# FOC.net
KiCad netlist of a schematic drawn in Altium Designer
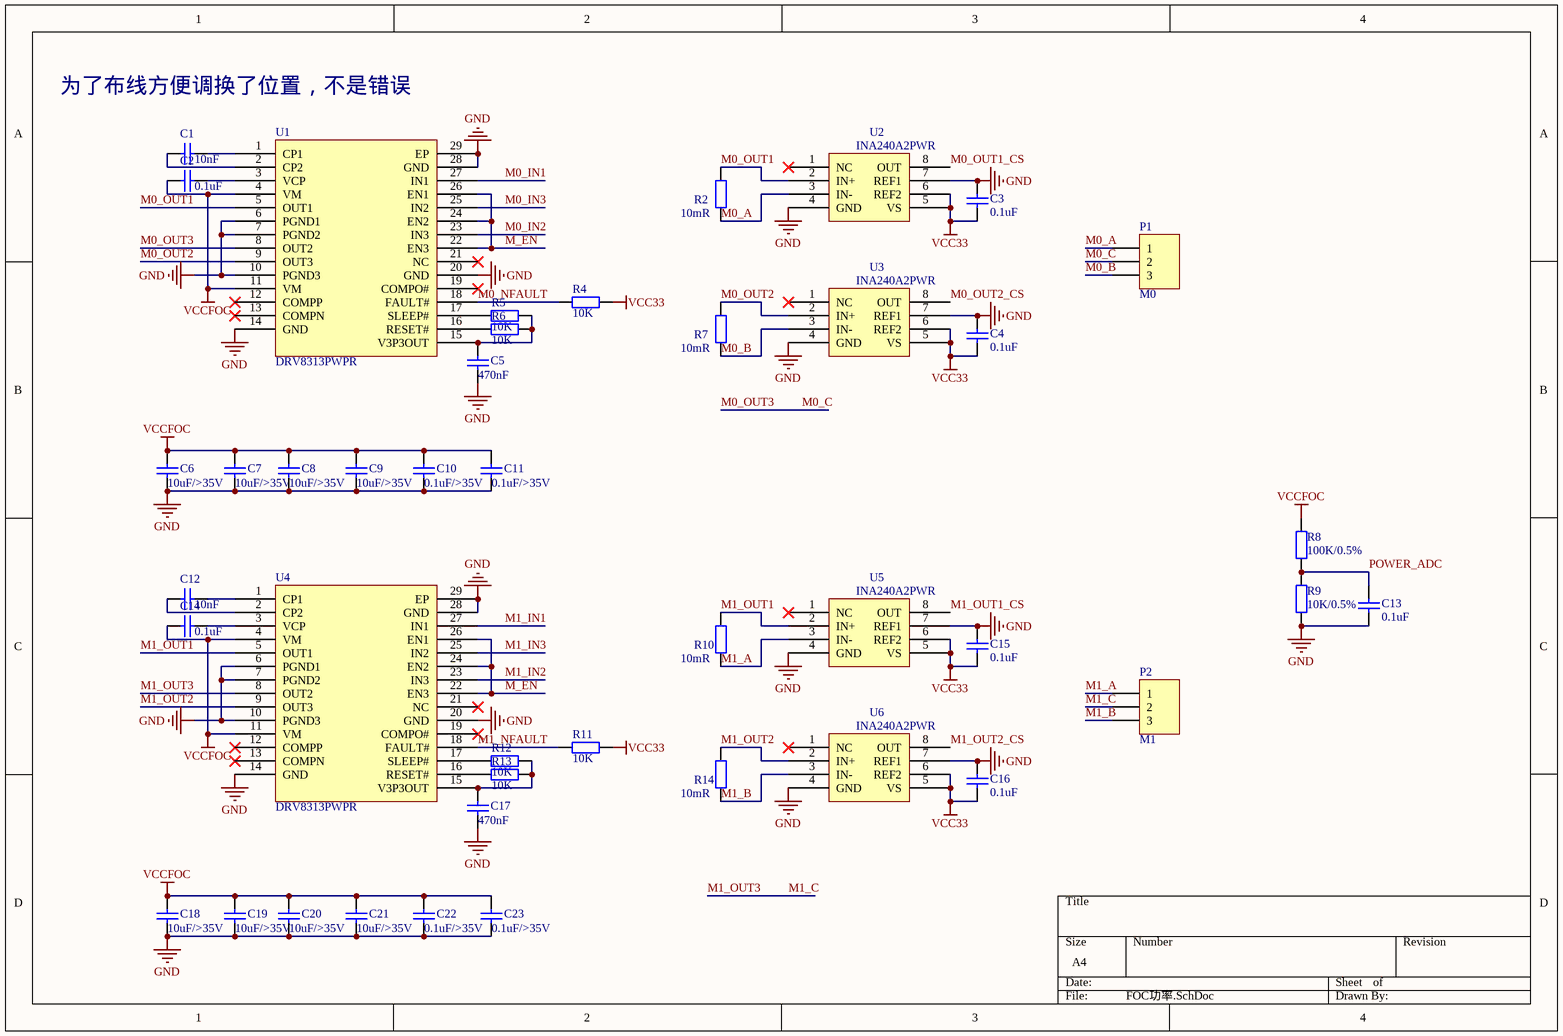
[diagram p0: FOC功率.SchDoc]

(export (version "E")
  (design (tool "Eeschema 10.0.6"))
  (components
    (comp (ref "C1")
      (value "10nF")
      (footprint "C0805_M")
      (description "Capacitor")
      (fields (field (name "PUBLISHER") "Altium Limited"))
      (libsource (lib "Miscellaneous Devices") (part "Cap"))
    )
    (comp (ref "C2")
      (value "0.1uF")
      (footprint "C0805_M")
      (description "Capacitor")
      (fields (field (name "PUBLISHER") "Altium Limited"))
      (libsource (lib "Miscellaneous Devices") (part "Cap"))
    )
    (comp (ref "C3")
      (value "0.1uF")
      (footprint "C0805_M")
      (description "Capacitor")
      (fields (field (name "PUBLISHER") "Altium Limited"))
      (libsource (lib "Miscellaneous Devices") (part "Cap"))
    )
    (comp (ref "C4")
      (value "0.1uF")
      (footprint "C0805_M")
      (description "Capacitor")
      (fields (field (name "PUBLISHER") "Altium Limited"))
      (libsource (lib "Miscellaneous Devices") (part "Cap"))
    )
    (comp (ref "C5")
      (value "470nF")
      (footprint "C0805_M")
      (description "Capacitor")
      (fields (field (name "PUBLISHER") "Altium Limited"))
      (libsource (lib "Miscellaneous Devices") (part "Cap"))
    )
    (comp (ref "C6")
      (value "10uF/>35V")
      (footprint "C0805_M")
      (description "Capacitor")
      (fields (field (name "PUBLISHER") "Altium Limited"))
      (libsource (lib "Miscellaneous Devices") (part "Cap"))
    )
    (comp (ref "C7")
      (value "10uF/>35V")
      (footprint "C0805_M")
      (description "Capacitor")
      (fields (field (name "PUBLISHER") "Altium Limited"))
      (libsource (lib "Miscellaneous Devices") (part "Cap"))
    )
    (comp (ref "C8")
      (value "10uF/>35V")
      (footprint "C0805_M")
      (description "Capacitor")
      (fields (field (name "PUBLISHER") "Altium Limited"))
      (libsource (lib "Miscellaneous Devices") (part "Cap"))
    )
    (comp (ref "C9")
      (value "10uF/>35V")
      (footprint "C0805_M")
      (description "Capacitor")
      (fields (field (name "PUBLISHER") "Altium Limited"))
      (libsource (lib "Miscellaneous Devices") (part "Cap"))
    )
    (comp (ref "C10")
      (value "0.1uF/>35V")
      (footprint "C0805_M")
      (description "Capacitor")
      (fields (field (name "PUBLISHER") "Altium Limited"))
      (libsource (lib "Miscellaneous Devices") (part "Cap"))
    )
    (comp (ref "C11")
      (value "0.1uF/>35V")
      (footprint "C0805_M")
      (description "Capacitor")
      (fields (field (name "PUBLISHER") "Altium Limited"))
      (libsource (lib "Miscellaneous Devices") (part "Cap"))
    )
    (comp (ref "C12")
      (value "10nF")
      (footprint "C0805_M")
      (description "Capacitor")
      (fields (field (name "PUBLISHER") "Altium Limited"))
      (libsource (lib "Miscellaneous Devices") (part "Cap"))
    )
    (comp (ref "C13")
      (value "0.1uF")
      (footprint "C0805_M")
      (description "Capacitor")
      (fields (field (name "PUBLISHER") "Altium Limited"))
      (libsource (lib "Miscellaneous Devices") (part "Cap"))
    )
    (comp (ref "C14")
      (value "0.1uF")
      (footprint "C0805_M")
      (description "Capacitor")
      (fields (field (name "PUBLISHER") "Altium Limited"))
      (libsource (lib "Miscellaneous Devices") (part "Cap"))
    )
    (comp (ref "C15")
      (value "0.1uF")
      (footprint "C0805_M")
      (description "Capacitor")
      (fields (field (name "PUBLISHER") "Altium Limited"))
      (libsource (lib "Miscellaneous Devices") (part "Cap"))
    )
    (comp (ref "C16")
      (value "0.1uF")
      (footprint "C0805_M")
      (description "Capacitor")
      (fields (field (name "PUBLISHER") "Altium Limited"))
      (libsource (lib "Miscellaneous Devices") (part "Cap"))
    )
    (comp (ref "C17")
      (value "470nF")
      (footprint "C0805_M")
      (description "Capacitor")
      (fields (field (name "PUBLISHER") "Altium Limited"))
      (libsource (lib "Miscellaneous Devices") (part "Cap"))
    )
    (comp (ref "C18")
      (value "10uF/>35V")
      (footprint "C0805_M")
      (description "Capacitor")
      (fields (field (name "PUBLISHER") "Altium Limited"))
      (libsource (lib "Miscellaneous Devices") (part "Cap"))
    )
    (comp (ref "C19")
      (value "10uF/>35V")
      (footprint "C0805_M")
      (description "Capacitor")
      (fields (field (name "PUBLISHER") "Altium Limited"))
      (libsource (lib "Miscellaneous Devices") (part "Cap"))
    )
    (comp (ref "C20")
      (value "10uF/>35V")
      (footprint "C0805_M")
      (description "Capacitor")
      (fields (field (name "PUBLISHER") "Altium Limited"))
      (libsource (lib "Miscellaneous Devices") (part "Cap"))
    )
    (comp (ref "C21")
      (value "10uF/>35V")
      (footprint "C0805_M")
      (description "Capacitor")
      (fields (field (name "PUBLISHER") "Altium Limited"))
      (libsource (lib "Miscellaneous Devices") (part "Cap"))
    )
    (comp (ref "C22")
      (value "0.1uF/>35V")
      (footprint "C0805_M")
      (description "Capacitor")
      (fields (field (name "PUBLISHER") "Altium Limited"))
      (libsource (lib "Miscellaneous Devices") (part "Cap"))
    )
    (comp (ref "C23")
      (value "0.1uF/>35V")
      (footprint "C0805_M")
      (description "Capacitor")
      (fields (field (name "PUBLISHER") "Altium Limited"))
      (libsource (lib "Miscellaneous Devices") (part "Cap"))
    )
    (comp (ref "P1")
      (value "M0")
      (footprint "MR30PB-F")
      (description "Header, 3-Pin")
      (fields (field (name "PUBLISHER") "Altium Limited"))
      (libsource (lib "Miscellaneous Connectors") (part "Header 3"))
    )
    (comp (ref "P2")
      (value "M1")
      (footprint "MR30PB-F")
      (description "Header, 3-Pin")
      (fields (field (name "PUBLISHER") "Altium Limited"))
      (libsource (lib "Miscellaneous Connectors") (part "Header 3"))
    )
    (comp (ref "R2")
      (value "10mR")
      (footprint "R1206_M")
      (description "Resistor")
      (fields (field (name "PUBLISHER") "Altium Limited"))
      (libsource (lib "") (part "Res2_1"))
    )
    (comp (ref "R4")
      (value "10K")
      (footprint "R0805_M")
      (description "Resistor")
      (fields (field (name "PUBLISHER") "Altium Limited"))
      (libsource (lib "Miscellaneous Devices") (part "Res2"))
    )
    (comp (ref "R5")
      (value "10K")
      (footprint "R0805_M")
      (description "Resistor")
      (fields (field (name "PUBLISHER") "Altium Limited"))
      (libsource (lib "Miscellaneous Devices") (part "Res2"))
    )
    (comp (ref "R6")
      (value "10K")
      (footprint "R0805_M")
      (description "Resistor")
      (fields (field (name "PUBLISHER") "Altium Limited"))
      (libsource (lib "Miscellaneous Devices") (part "Res2"))
    )
    (comp (ref "R7")
      (value "10mR")
      (footprint "R1206_M")
      (description "Resistor")
      (fields (field (name "PUBLISHER") "Altium Limited"))
      (libsource (lib "") (part "Res2_1"))
    )
    (comp (ref "R8")
      (value "100K/0.5%")
      (footprint "R0805_M")
      (description "Resistor")
      (fields (field (name "PUBLISHER") "Altium Limited"))
      (libsource (lib "") (part "Res2_2"))
    )
    (comp (ref "R9")
      (value "10K/0.5%")
      (footprint "R0805_M")
      (description "Resistor")
      (fields (field (name "PUBLISHER") "Altium Limited"))
      (libsource (lib "") (part "Res2_2"))
    )
    (comp (ref "R10")
      (value "10mR")
      (footprint "R1206_M")
      (description "Resistor")
      (fields (field (name "PUBLISHER") "Altium Limited"))
      (libsource (lib "") (part "Res2_1"))
    )
    (comp (ref "R11")
      (value "10K")
      (footprint "R0805_M")
      (description "Resistor")
      (fields (field (name "PUBLISHER") "Altium Limited"))
      (libsource (lib "Miscellaneous Devices") (part "Res2"))
    )
    (comp (ref "R12")
      (value "10K")
      (footprint "R0805_M")
      (description "Resistor")
      (fields (field (name "PUBLISHER") "Altium Limited"))
      (libsource (lib "Miscellaneous Devices") (part "Res2"))
    )
    (comp (ref "R13")
      (value "10K")
      (footprint "R0805_M")
      (description "Resistor")
      (fields (field (name "PUBLISHER") "Altium Limited"))
      (libsource (lib "Miscellaneous Devices") (part "Res2"))
    )
    (comp (ref "R14")
      (value "10mR")
      (footprint "R1206_M")
      (description "Resistor")
      (fields (field (name "PUBLISHER") "Altium Limited"))
      (libsource (lib "") (part "Res2_1"))
    )
    (comp (ref "U1")
      (value "DRV8313PWPR")
      (footprint "TSSOP28-PowerPad")
      (libsource (lib "XL6005") (part "DRV8313PWPR"))
    )
    (comp (ref "U2")
      (value "INA240A2PWR")
      (footprint "TSSOP8")
      (libsource (lib "XL6005") (part "Component_3"))
    )
    (comp (ref "U3")
      (value "INA240A2PWR")
      (footprint "TSSOP8")
      (libsource (lib "XL6005") (part "Component_3"))
    )
    (comp (ref "U4")
      (value "DRV8313PWPR")
      (footprint "TSSOP28-PowerPad")
      (libsource (lib "XL6005") (part "DRV8313PWPR"))
    )
    (comp (ref "U5")
      (value "INA240A2PWR")
      (footprint "TSSOP8")
      (libsource (lib "XL6005") (part "Component_3"))
    )
    (comp (ref "U6")
      (value "INA240A2PWR")
      (footprint "TSSOP8")
      (libsource (lib "XL6005") (part "Component_3"))
    )
  )
  (nets
    (net (code "1") (name "/M0_A") (class "Default")
      (node (ref "P1") (pin "1") (pinfunction "1_1") (pintype "passive"))
      (node (ref "R2") (pin "1") (pinfunction "1_1") (pintype "passive"))
      (node (ref "U2") (pin "3") (pinfunction "IN-_3") (pintype "passive"))
    )
    (net (code "2") (name "/M0_B") (class "Default")
      (node (ref "P1") (pin "3") (pinfunction "3_3") (pintype "passive"))
      (node (ref "R7") (pin "1") (pinfunction "1_1") (pintype "passive"))
      (node (ref "U3") (pin "3") (pinfunction "IN-_3") (pintype "passive"))
    )
    (net (code "3") (name "/M0_C") (class "Default")
      (node (ref "P1") (pin "2") (pinfunction "2_2") (pintype "passive"))
      (node (ref "U1") (pin "8") (pinfunction "OUT2_8") (pintype "passive"))
    )
    (net (code "4") (name "/M0_IN1") (class "Default")
      (node (ref "U1") (pin "27") (pinfunction "IN1_27") (pintype "passive"))
    )
    (net (code "5") (name "/M0_IN2") (class "Default")
      (node (ref "U1") (pin "23") (pinfunction "IN3_23") (pintype "passive"))
    )
    (net (code "6") (name "/M0_IN3") (class "Default")
      (node (ref "U1") (pin "25") (pinfunction "IN2_25") (pintype "passive"))
    )
    (net (code "7") (name "/M0_NFAULT") (class "Default")
      (node (ref "R4") (pin "1") (pinfunction "1_1") (pintype "passive"))
      (node (ref "U1") (pin "18") (pinfunction "FAULT#_18") (pintype "passive"))
    )
    (net (code "8") (name "/M0_OUT1") (class "Default")
      (node (ref "R2") (pin "2") (pinfunction "2_2") (pintype "passive"))
      (node (ref "U1") (pin "5") (pinfunction "OUT1_5") (pintype "passive"))
      (node (ref "U2") (pin "2") (pinfunction "IN+_2") (pintype "passive"))
    )
    (net (code "9") (name "/M0_OUT1_CS") (class "Default")
      (node (ref "U2") (pin "8") (pinfunction "OUT_8") (pintype "passive"))
    )
    (net (code "10") (name "/M0_OUT2") (class "Default")
      (node (ref "R7") (pin "2") (pinfunction "2_2") (pintype "passive"))
      (node (ref "U1") (pin "9") (pinfunction "OUT3_9") (pintype "passive"))
      (node (ref "U3") (pin "2") (pinfunction "IN+_2") (pintype "passive"))
    )
    (net (code "11") (name "/M0_OUT2_CS") (class "Default")
      (node (ref "U3") (pin "8") (pinfunction "OUT_8") (pintype "passive"))
    )
    (net (code "12") (name "/M1_A") (class "Default")
      (node (ref "P2") (pin "1") (pinfunction "1_1") (pintype "passive"))
      (node (ref "R10") (pin "1") (pinfunction "1_1") (pintype "passive"))
      (node (ref "U5") (pin "3") (pinfunction "IN-_3") (pintype "passive"))
    )
    (net (code "13") (name "/M1_B") (class "Default")
      (node (ref "P2") (pin "3") (pinfunction "3_3") (pintype "passive"))
      (node (ref "R14") (pin "1") (pinfunction "1_1") (pintype "passive"))
      (node (ref "U6") (pin "3") (pinfunction "IN-_3") (pintype "passive"))
    )
    (net (code "14") (name "/M1_C") (class "Default")
      (node (ref "P2") (pin "2") (pinfunction "2_2") (pintype "passive"))
      (node (ref "U4") (pin "8") (pinfunction "OUT2_8") (pintype "passive"))
    )
    (net (code "15") (name "/M1_IN1") (class "Default")
      (node (ref "U4") (pin "27") (pinfunction "IN1_27") (pintype "passive"))
    )
    (net (code "16") (name "/M1_IN2") (class "Default")
      (node (ref "U4") (pin "23") (pinfunction "IN3_23") (pintype "passive"))
    )
    (net (code "17") (name "/M1_IN3") (class "Default")
      (node (ref "U4") (pin "25") (pinfunction "IN2_25") (pintype "passive"))
    )
    (net (code "18") (name "/M1_NFAULT") (class "Default")
      (node (ref "R11") (pin "1") (pinfunction "1_1") (pintype "passive"))
      (node (ref "U4") (pin "18") (pinfunction "FAULT#_18") (pintype "passive"))
    )
    (net (code "19") (name "/M1_OUT1") (class "Default")
      (node (ref "R10") (pin "2") (pinfunction "2_2") (pintype "passive"))
      (node (ref "U4") (pin "5") (pinfunction "OUT1_5") (pintype "passive"))
      (node (ref "U5") (pin "2") (pinfunction "IN+_2") (pintype "passive"))
    )
    (net (code "20") (name "/M1_OUT1_CS") (class "Default")
      (node (ref "U5") (pin "8") (pinfunction "OUT_8") (pintype "passive"))
    )
    (net (code "21") (name "/M1_OUT2") (class "Default")
      (node (ref "R14") (pin "2") (pinfunction "2_2") (pintype "passive"))
      (node (ref "U4") (pin "9") (pinfunction "OUT3_9") (pintype "passive"))
      (node (ref "U6") (pin "2") (pinfunction "IN+_2") (pintype "passive"))
    )
    (net (code "22") (name "/M1_OUT2_CS") (class "Default")
      (node (ref "U6") (pin "8") (pinfunction "OUT_8") (pintype "passive"))
    )
    (net (code "23") (name "/M_EN") (class "Default")
      (node (ref "U1") (pin "22") (pinfunction "EN3_22") (pintype "passive"))
      (node (ref "U1") (pin "24") (pinfunction "EN2_24") (pintype "passive"))
      (node (ref "U1") (pin "26") (pinfunction "EN1_26") (pintype "passive"))
      (node (ref "U4") (pin "22") (pinfunction "EN3_22") (pintype "passive"))
      (node (ref "U4") (pin "24") (pinfunction "EN2_24") (pintype "passive"))
      (node (ref "U4") (pin "26") (pinfunction "EN1_26") (pintype "passive"))
    )
    (net (code "24") (name "/POWER_ADC") (class "Default")
      (node (ref "C13") (pin "2") (pinfunction "2_2") (pintype "passive"))
      (node (ref "R8") (pin "2") (pinfunction "2_2") (pintype "passive"))
      (node (ref "R9") (pin "1") (pinfunction "1_1") (pintype "passive"))
    )
    (net (code "25") (name "GND") (class "Default")
      (node (ref "C10") (pin "1") (pinfunction "1_1") (pintype "passive"))
      (node (ref "C11") (pin "1") (pinfunction "1_1") (pintype "passive"))
      (node (ref "C13") (pin "1") (pinfunction "1_1") (pintype "passive"))
      (node (ref "C15") (pin "2") (pinfunction "2_2") (pintype "passive"))
      (node (ref "C16") (pin "2") (pinfunction "2_2") (pintype "passive"))
      (node (ref "C17") (pin "1") (pinfunction "1_1") (pintype "passive"))
      (node (ref "C18") (pin "1") (pinfunction "1_1") (pintype "passive"))
      (node (ref "C19") (pin "1") (pinfunction "1_1") (pintype "passive"))
      (node (ref "C20") (pin "1") (pinfunction "1_1") (pintype "passive"))
      (node (ref "C21") (pin "1") (pinfunction "1_1") (pintype "passive"))
      (node (ref "C22") (pin "1") (pinfunction "1_1") (pintype "passive"))
      (node (ref "C23") (pin "1") (pinfunction "1_1") (pintype "passive"))
      (node (ref "C3") (pin "2") (pinfunction "2_2") (pintype "passive"))
      (node (ref "C4") (pin "2") (pinfunction "2_2") (pintype "passive"))
      (node (ref "C5") (pin "1") (pinfunction "1_1") (pintype "passive"))
      (node (ref "C6") (pin "1") (pinfunction "1_1") (pintype "passive"))
      (node (ref "C7") (pin "1") (pinfunction "1_1") (pintype "passive"))
      (node (ref "C8") (pin "1") (pinfunction "1_1") (pintype "passive"))
      (node (ref "C9") (pin "1") (pinfunction "1_1") (pintype "passive"))
      (node (ref "R9") (pin "2") (pinfunction "2_2") (pintype "passive"))
      (node (ref "U1") (pin "10") (pinfunction "PGND3_10") (pintype "passive"))
      (node (ref "U1") (pin "14") (pinfunction "GND_14") (pintype "passive"))
      (node (ref "U1") (pin "20") (pinfunction "GND_20") (pintype "passive"))
      (node (ref "U1") (pin "28") (pinfunction "GND_28") (pintype "passive"))
      (node (ref "U1") (pin "29") (pinfunction "EP_29") (pintype "passive"))
      (node (ref "U1") (pin "6") (pinfunction "PGND1_6") (pintype "passive"))
      (node (ref "U1") (pin "7") (pinfunction "PGND2_7") (pintype "passive"))
      (node (ref "U2") (pin "4") (pinfunction "GND_4") (pintype "passive"))
      (node (ref "U2") (pin "7") (pinfunction "REF1_7") (pintype "passive"))
      (node (ref "U3") (pin "4") (pinfunction "GND_4") (pintype "passive"))
      (node (ref "U3") (pin "7") (pinfunction "REF1_7") (pintype "passive"))
      (node (ref "U4") (pin "10") (pinfunction "PGND3_10") (pintype "passive"))
      (node (ref "U4") (pin "14") (pinfunction "GND_14") (pintype "passive"))
      (node (ref "U4") (pin "20") (pinfunction "GND_20") (pintype "passive"))
      (node (ref "U4") (pin "28") (pinfunction "GND_28") (pintype "passive"))
      (node (ref "U4") (pin "29") (pinfunction "EP_29") (pintype "passive"))
      (node (ref "U4") (pin "6") (pinfunction "PGND1_6") (pintype "passive"))
      (node (ref "U4") (pin "7") (pinfunction "PGND2_7") (pintype "passive"))
      (node (ref "U5") (pin "4") (pinfunction "GND_4") (pintype "passive"))
      (node (ref "U5") (pin "7") (pinfunction "REF1_7") (pintype "passive"))
      (node (ref "U6") (pin "4") (pinfunction "GND_4") (pintype "passive"))
      (node (ref "U6") (pin "7") (pinfunction "REF1_7") (pintype "passive"))
    )
    (net (code "26") (name "Net-(U1-CP1)") (class "Default")
      (node (ref "C1") (pin "2") (pinfunction "2_2") (pintype "passive"))
      (node (ref "U1") (pin "1") (pinfunction "CP1_1") (pintype "passive"))
    )
    (net (code "27") (name "Net-(U1-CP2)") (class "Default")
      (node (ref "C1") (pin "1") (pinfunction "1_1") (pintype "passive"))
      (node (ref "U1") (pin "2") (pinfunction "CP2_2") (pintype "passive"))
    )
    (net (code "28") (name "Net-(U1-RESET#)") (class "Default")
      (node (ref "R6") (pin "1") (pinfunction "1_1") (pintype "passive"))
      (node (ref "U1") (pin "16") (pinfunction "RESET#_16") (pintype "passive"))
    )
    (net (code "29") (name "Net-(U1-SLEEP#)") (class "Default")
      (node (ref "R5") (pin "1") (pinfunction "1_1") (pintype "passive"))
      (node (ref "U1") (pin "17") (pinfunction "SLEEP#_17") (pintype "passive"))
    )
    (net (code "30") (name "Net-(U1-V3P3OUT)") (class "Default")
      (node (ref "C5") (pin "2") (pinfunction "2_2") (pintype "passive"))
      (node (ref "R5") (pin "2") (pinfunction "2_2") (pintype "passive"))
      (node (ref "R6") (pin "2") (pinfunction "2_2") (pintype "passive"))
      (node (ref "U1") (pin "15") (pinfunction "V3P3OUT_15") (pintype "passive"))
    )
    (net (code "31") (name "Net-(U1-VCP)") (class "Default")
      (node (ref "C2") (pin "2") (pinfunction "2_2") (pintype "passive"))
      (node (ref "U1") (pin "3") (pinfunction "VCP_3") (pintype "passive"))
    )
    (net (code "32") (name "Net-(U4-CP1)") (class "Default")
      (node (ref "C12") (pin "2") (pinfunction "2_2") (pintype "passive"))
      (node (ref "U4") (pin "1") (pinfunction "CP1_1") (pintype "passive"))
    )
    (net (code "33") (name "Net-(U4-CP2)") (class "Default")
      (node (ref "C12") (pin "1") (pinfunction "1_1") (pintype "passive"))
      (node (ref "U4") (pin "2") (pinfunction "CP2_2") (pintype "passive"))
    )
    (net (code "34") (name "Net-(U4-RESET#)") (class "Default")
      (node (ref "R13") (pin "1") (pinfunction "1_1") (pintype "passive"))
      (node (ref "U4") (pin "16") (pinfunction "RESET#_16") (pintype "passive"))
    )
    (net (code "35") (name "Net-(U4-SLEEP#)") (class "Default")
      (node (ref "R12") (pin "1") (pinfunction "1_1") (pintype "passive"))
      (node (ref "U4") (pin "17") (pinfunction "SLEEP#_17") (pintype "passive"))
    )
    (net (code "36") (name "Net-(U4-V3P3OUT)") (class "Default")
      (node (ref "C17") (pin "2") (pinfunction "2_2") (pintype "passive"))
      (node (ref "R12") (pin "2") (pinfunction "2_2") (pintype "passive"))
      (node (ref "R13") (pin "2") (pinfunction "2_2") (pintype "passive"))
      (node (ref "U4") (pin "15") (pinfunction "V3P3OUT_15") (pintype "passive"))
    )
    (net (code "37") (name "Net-(U4-VCP)") (class "Default")
      (node (ref "C14") (pin "2") (pinfunction "2_2") (pintype "passive"))
      (node (ref "U4") (pin "3") (pinfunction "VCP_3") (pintype "passive"))
    )
    (net (code "38") (name "VCC33") (class "Default")
      (node (ref "C15") (pin "1") (pinfunction "1_1") (pintype "passive"))
      (node (ref "C16") (pin "1") (pinfunction "1_1") (pintype "passive"))
      (node (ref "C3") (pin "1") (pinfunction "1_1") (pintype "passive"))
      (node (ref "C4") (pin "1") (pinfunction "1_1") (pintype "passive"))
      (node (ref "R11") (pin "2") (pinfunction "2_2") (pintype "passive"))
      (node (ref "R4") (pin "2") (pinfunction "2_2") (pintype "passive"))
      (node (ref "U2") (pin "5") (pinfunction "VS_5") (pintype "passive"))
      (node (ref "U2") (pin "6") (pinfunction "REF2_6") (pintype "passive"))
      (node (ref "U3") (pin "5") (pinfunction "VS_5") (pintype "passive"))
      (node (ref "U3") (pin "6") (pinfunction "REF2_6") (pintype "passive"))
      (node (ref "U5") (pin "5") (pinfunction "VS_5") (pintype "passive"))
      (node (ref "U5") (pin "6") (pinfunction "REF2_6") (pintype "passive"))
      (node (ref "U6") (pin "5") (pinfunction "VS_5") (pintype "passive"))
      (node (ref "U6") (pin "6") (pinfunction "REF2_6") (pintype "passive"))
    )
    (net (code "39") (name "VCCFOC") (class "Default")
      (node (ref "C10") (pin "2") (pinfunction "2_2") (pintype "passive"))
      (node (ref "C11") (pin "2") (pinfunction "2_2") (pintype "passive"))
      (node (ref "C14") (pin "1") (pinfunction "1_1") (pintype "passive"))
      (node (ref "C18") (pin "2") (pinfunction "2_2") (pintype "passive"))
      (node (ref "C19") (pin "2") (pinfunction "2_2") (pintype "passive"))
      (node (ref "C2") (pin "1") (pinfunction "1_1") (pintype "passive"))
      (node (ref "C20") (pin "2") (pinfunction "2_2") (pintype "passive"))
      (node (ref "C21") (pin "2") (pinfunction "2_2") (pintype "passive"))
      (node (ref "C22") (pin "2") (pinfunction "2_2") (pintype "passive"))
      (node (ref "C23") (pin "2") (pinfunction "2_2") (pintype "passive"))
      (node (ref "C6") (pin "2") (pinfunction "2_2") (pintype "passive"))
      (node (ref "C7") (pin "2") (pinfunction "2_2") (pintype "passive"))
      (node (ref "C8") (pin "2") (pinfunction "2_2") (pintype "passive"))
      (node (ref "C9") (pin "2") (pinfunction "2_2") (pintype "passive"))
      (node (ref "R8") (pin "1") (pinfunction "1_1") (pintype "passive"))
      (node (ref "U1") (pin "11") (pinfunction "VM_11") (pintype "passive"))
      (node (ref "U1") (pin "4") (pinfunction "VM_4") (pintype "passive"))
      (node (ref "U4") (pin "11") (pinfunction "VM_11") (pintype "passive"))
      (node (ref "U4") (pin "4") (pinfunction "VM_4") (pintype "passive"))
    )
    (net (code "40") (name "unconnected-(U1-COMPN-Pad13)") (class "Default")
      (node (ref "U1") (pin "13") (pinfunction "COMPN_13") (pintype "passive+no_connect"))
    )
    (net (code "41") (name "unconnected-(U1-COMPO#-Pad19)") (class "Default")
      (node (ref "U1") (pin "19") (pinfunction "COMPO#_19") (pintype "passive+no_connect"))
    )
    (net (code "42") (name "unconnected-(U1-COMPP-Pad12)") (class "Default")
      (node (ref "U1") (pin "12") (pinfunction "COMPP_12") (pintype "passive+no_connect"))
    )
    (net (code "43") (name "unconnected-(U1-NC-Pad21)") (class "Default")
      (node (ref "U1") (pin "21") (pinfunction "NC_21") (pintype "passive+no_connect"))
    )
    (net (code "44") (name "unconnected-(U2-NC-Pad1)") (class "Default")
      (node (ref "U2") (pin "1") (pinfunction "NC_1") (pintype "passive+no_connect"))
    )
    (net (code "45") (name "unconnected-(U3-NC-Pad1)") (class "Default")
      (node (ref "U3") (pin "1") (pinfunction "NC_1") (pintype "passive+no_connect"))
    )
    (net (code "46") (name "unconnected-(U4-COMPN-Pad13)") (class "Default")
      (node (ref "U4") (pin "13") (pinfunction "COMPN_13") (pintype "passive+no_connect"))
    )
    (net (code "47") (name "unconnected-(U4-COMPO#-Pad19)") (class "Default")
      (node (ref "U4") (pin "19") (pinfunction "COMPO#_19") (pintype "passive+no_connect"))
    )
    (net (code "48") (name "unconnected-(U4-COMPP-Pad12)") (class "Default")
      (node (ref "U4") (pin "12") (pinfunction "COMPP_12") (pintype "passive+no_connect"))
    )
    (net (code "49") (name "unconnected-(U4-NC-Pad21)") (class "Default")
      (node (ref "U4") (pin "21") (pinfunction "NC_21") (pintype "passive+no_connect"))
    )
    (net (code "50") (name "unconnected-(U5-NC-Pad1)") (class "Default")
      (node (ref "U5") (pin "1") (pinfunction "NC_1") (pintype "passive+no_connect"))
    )
    (net (code "51") (name "unconnected-(U6-NC-Pad1)") (class "Default")
      (node (ref "U6") (pin "1") (pinfunction "NC_1") (pintype "passive+no_connect"))
    )
  )
)
